# AD5686R.net
KiCad netlist of a schematic drawn in Altium Designer
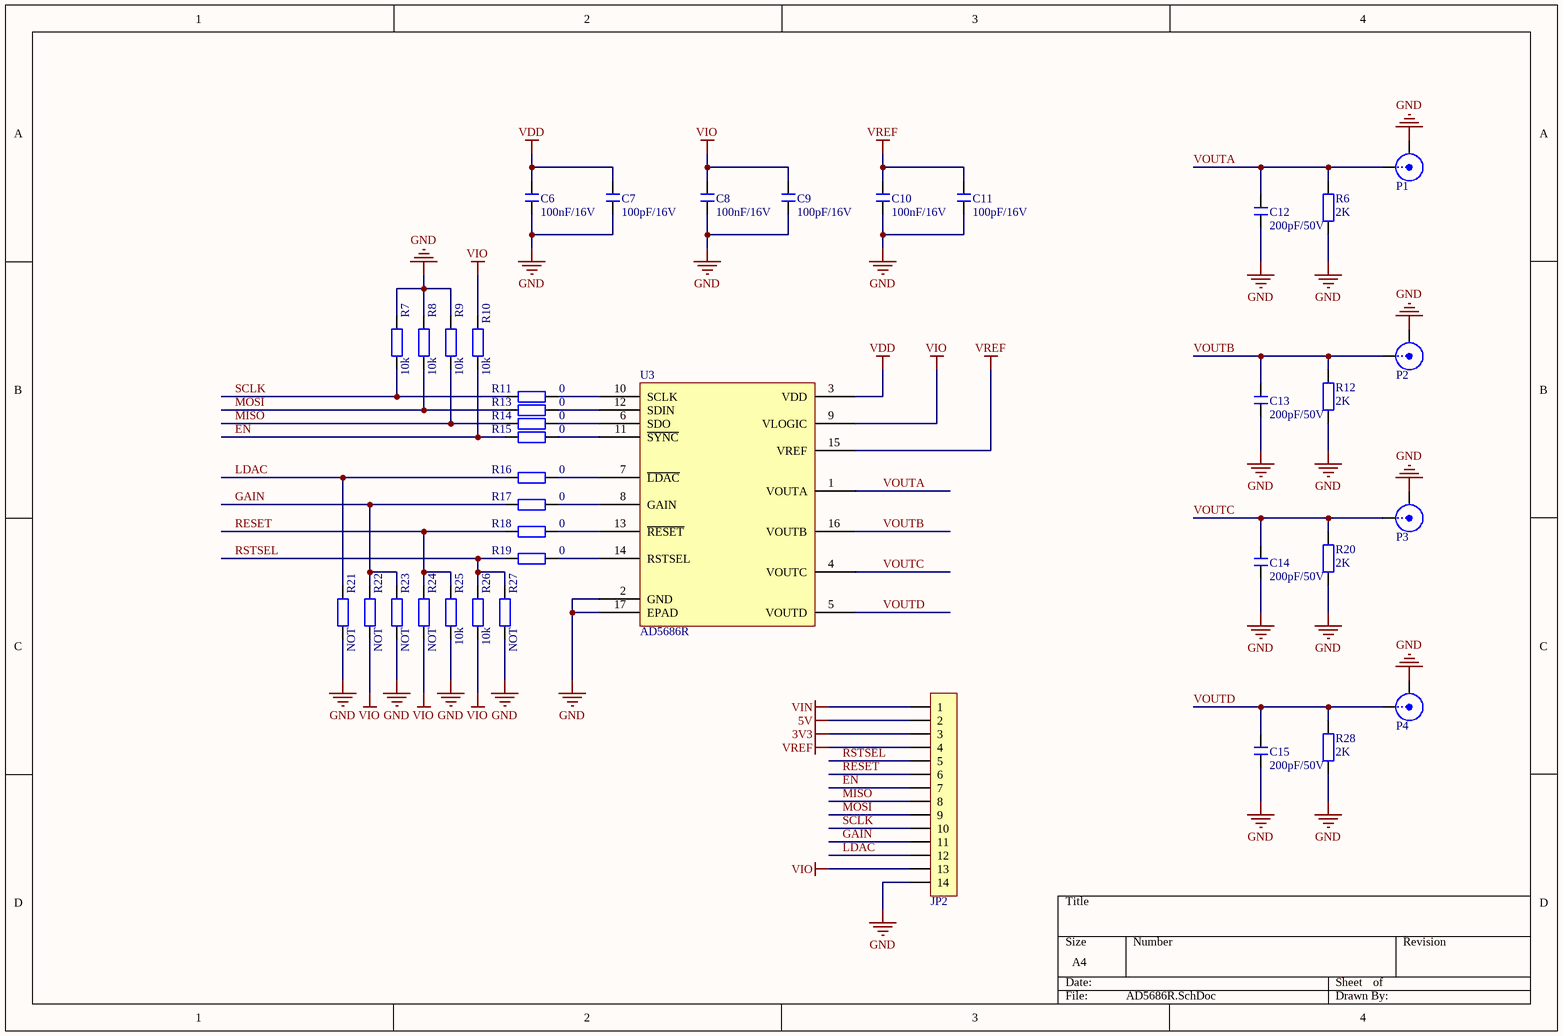
[diagram p0: AD5686R.SchDoc]

(export (version "E")
  (design (tool "Eeschema 10.0.6"))
  (components
    (comp (ref "C6")
      (value "100nF/16V")
      (footprint "C 0402_L")
      (description "贴片电容")
      (libsource (lib "3.1   - 电阻-电容-电感") (part "C"))
    )
    (comp (ref "C7")
      (value "100pF/16V")
      (footprint "C 0402_L")
      (description "贴片电容")
      (libsource (lib "3.1   - 电阻-电容-电感") (part "C"))
    )
    (comp (ref "C8")
      (value "100nF/16V")
      (footprint "C 0402_L")
      (description "贴片电容")
      (libsource (lib "3.1   - 电阻-电容-电感") (part "C"))
    )
    (comp (ref "C9")
      (value "100pF/16V")
      (footprint "C 0402_L")
      (description "贴片电容")
      (libsource (lib "3.1   - 电阻-电容-电感") (part "C"))
    )
    (comp (ref "C10")
      (value "100nF/16V")
      (footprint "C 0402_L")
      (description "贴片电容")
      (libsource (lib "3.1   - 电阻-电容-电感") (part "C"))
    )
    (comp (ref "C11")
      (value "100pF/16V")
      (footprint "C 0402_L")
      (description "贴片电容")
      (libsource (lib "3.1   - 电阻-电容-电感") (part "C"))
    )
    (comp (ref "C12")
      (value "200pF/50V")
      (footprint "C 0402_L")
      (description "贴片电容")
      (libsource (lib "3.1   - 电阻-电容-电感") (part "C"))
    )
    (comp (ref "C13")
      (value "200pF/50V")
      (footprint "C 0402_L")
      (description "贴片电容")
      (libsource (lib "3.1   - 电阻-电容-电感") (part "C"))
    )
    (comp (ref "C14")
      (value "200pF/50V")
      (footprint "C 0402_L")
      (description "贴片电容")
      (libsource (lib "3.1   - 电阻-电容-电感") (part "C"))
    )
    (comp (ref "C15")
      (value "200pF/50V")
      (footprint "C 0402_L")
      (description "贴片电容")
      (libsource (lib "3.1   - 电阻-电容-电感") (part "C"))
    )
    (comp (ref "JP2")
      (value "HDR-1X14")
      (footprint "HDR2.54-LI-14P")
      (description "14P接插件")
      (fields (field (name "版权归属") "源创客"))
      (libsource (lib "4.5   - 接插件-脚距2.54") (part "Header 14"))
    )
    (comp (ref "P1")
      (value "SMB")
      (footprint "SMA")
      (description "SMB Straight Connector")
      (libsource (lib "Miscellaneous Connectors") (part "SMB"))
    )
    (comp (ref "P2")
      (value "SMB")
      (footprint "SMA")
      (description "SMB Straight Connector")
      (libsource (lib "Miscellaneous Connectors") (part "SMB"))
    )
    (comp (ref "P3")
      (value "SMB")
      (footprint "SMA")
      (description "SMB Straight Connector")
      (libsource (lib "Miscellaneous Connectors") (part "SMB"))
    )
    (comp (ref "P4")
      (value "SMB")
      (footprint "SMA")
      (description "SMB Straight Connector")
      (libsource (lib "Miscellaneous Connectors") (part "SMB"))
    )
    (comp (ref "R6")
      (value "2K")
      (footprint "R 0402_L")
      (description "贴片电阻 0402 1%")
      (libsource (lib "3.1   - 电阻-电容-电感") (part "R"))
    )
    (comp (ref "R7")
      (value "10k")
      (footprint "R 0402_L")
      (description "贴片电阻")
      (libsource (lib "3.1   - 电阻-电容-电感") (part "R"))
    )
    (comp (ref "R8")
      (value "10k")
      (footprint "R 0402_L")
      (description "贴片电阻")
      (libsource (lib "3.1   - 电阻-电容-电感") (part "R"))
    )
    (comp (ref "R9")
      (value "10k")
      (footprint "R 0402_L")
      (description "贴片电阻")
      (libsource (lib "3.1   - 电阻-电容-电感") (part "R"))
    )
    (comp (ref "R10")
      (value "10k")
      (footprint "R 0402_L")
      (description "贴片电阻")
      (libsource (lib "3.1   - 电阻-电容-电感") (part "R"))
    )
    (comp (ref "R11")
      (value "0")
      (footprint "R 0402_L")
      (description "贴片电阻 0402 1%")
      (libsource (lib "3.1   - 电阻-电容-电感") (part "R"))
    )
    (comp (ref "R12")
      (value "2K")
      (footprint "R 0402_L")
      (description "贴片电阻 0402 1%")
      (libsource (lib "3.1   - 电阻-电容-电感") (part "R"))
    )
    (comp (ref "R13")
      (value "0")
      (footprint "R 0402_L")
      (description "贴片电阻 0402 1%")
      (libsource (lib "3.1   - 电阻-电容-电感") (part "R"))
    )
    (comp (ref "R14")
      (value "0")
      (footprint "R 0402_L")
      (description "贴片电阻 0402 1%")
      (libsource (lib "3.1   - 电阻-电容-电感") (part "R"))
    )
    (comp (ref "R15")
      (value "0")
      (footprint "R 0402_L")
      (description "贴片电阻 0402 1%")
      (libsource (lib "3.1   - 电阻-电容-电感") (part "R"))
    )
    (comp (ref "R16")
      (value "0")
      (footprint "R 0402_L")
      (description "贴片电阻 0402 1%")
      (libsource (lib "3.1   - 电阻-电容-电感") (part "R"))
    )
    (comp (ref "R17")
      (value "0")
      (footprint "R 0402_L")
      (description "贴片电阻 0402 1%")
      (libsource (lib "3.1   - 电阻-电容-电感") (part "R"))
    )
    (comp (ref "R18")
      (value "0")
      (footprint "R 0402_L")
      (description "贴片电阻 0402 1%")
      (libsource (lib "3.1   - 电阻-电容-电感") (part "R"))
    )
    (comp (ref "R19")
      (value "0")
      (footprint "R 0402_L")
      (description "贴片电阻 0402 1%")
      (libsource (lib "3.1   - 电阻-电容-电感") (part "R"))
    )
    (comp (ref "R20")
      (value "2K")
      (footprint "R 0402_L")
      (description "贴片电阻 0402 1%")
      (libsource (lib "3.1   - 电阻-电容-电感") (part "R"))
    )
    (comp (ref "R21")
      (value "NOT")
      (footprint "R 0402_L")
      (description "贴片电阻")
      (libsource (lib "3.1   - 电阻-电容-电感") (part "R"))
    )
    (comp (ref "R22")
      (value "NOT")
      (footprint "R 0402_L")
      (description "贴片电阻")
      (libsource (lib "3.1   - 电阻-电容-电感") (part "R"))
    )
    (comp (ref "R23")
      (value "NOT")
      (footprint "R 0402_L")
      (description "贴片电阻")
      (libsource (lib "3.1   - 电阻-电容-电感") (part "R"))
    )
    (comp (ref "R24")
      (value "NOT")
      (footprint "R 0402_L")
      (description "贴片电阻")
      (libsource (lib "3.1   - 电阻-电容-电感") (part "R"))
    )
    (comp (ref "R25")
      (value "10k")
      (footprint "R 0402_L")
      (description "贴片电阻")
      (libsource (lib "3.1   - 电阻-电容-电感") (part "R"))
    )
    (comp (ref "R26")
      (value "10k")
      (footprint "R 0402_L")
      (description "贴片电阻")
      (libsource (lib "3.1   - 电阻-电容-电感") (part "R"))
    )
    (comp (ref "R27")
      (value "NOT")
      (footprint "R 0402_L")
      (description "贴片电阻")
      (libsource (lib "3.1   - 电阻-电容-电感") (part "R"))
    )
    (comp (ref "R28")
      (value "2K")
      (footprint "R 0402_L")
      (description "贴片电阻 0402 1%")
      (libsource (lib "3.1   - 电阻-电容-电感") (part "R"))
    )
    (comp (ref "U3") (value "AD5686R") (footprint "AD5686R") (libsource (lib "Schlib1") (part "AD5686R")))
  )
  (nets
    (net (code "1") (name "/EN") (class "Default")
      (node (ref "JP2") (pin "7") (pinfunction "7_7") (pintype "passive"))
      (node (ref "R10") (pin "2") (pinfunction "2_2") (pintype "passive"))
      (node (ref "R15") (pin "2") (pinfunction "2_2") (pintype "passive"))
    )
    (net (code "2") (name "/GAIN") (class "Default")
      (node (ref "JP2") (pin "11") (pinfunction "11_11") (pintype "passive"))
      (node (ref "R17") (pin "2") (pinfunction "2_2") (pintype "passive"))
      (node (ref "R22") (pin "2") (pinfunction "2_2") (pintype "passive"))
      (node (ref "R23") (pin "2") (pinfunction "2_2") (pintype "passive"))
    )
    (net (code "3") (name "/LDAC") (class "Default")
      (node (ref "JP2") (pin "12") (pinfunction "12_12") (pintype "passive"))
      (node (ref "R16") (pin "2") (pinfunction "2_2") (pintype "passive"))
      (node (ref "R21") (pin "2") (pinfunction "2_2") (pintype "passive"))
    )
    (net (code "4") (name "/MISO") (class "Default")
      (node (ref "JP2") (pin "8") (pinfunction "8_8") (pintype "passive"))
      (node (ref "R14") (pin "2") (pinfunction "2_2") (pintype "passive"))
      (node (ref "R9") (pin "2") (pinfunction "2_2") (pintype "passive"))
    )
    (net (code "5") (name "/MOSI") (class "Default")
      (node (ref "JP2") (pin "9") (pinfunction "9_9") (pintype "passive"))
      (node (ref "R13") (pin "2") (pinfunction "2_2") (pintype "passive"))
      (node (ref "R8") (pin "2") (pinfunction "2_2") (pintype "passive"))
    )
    (net (code "6") (name "/RESET") (class "Default")
      (node (ref "JP2") (pin "6") (pinfunction "6_6") (pintype "passive"))
      (node (ref "R18") (pin "2") (pinfunction "2_2") (pintype "passive"))
      (node (ref "R24") (pin "2") (pinfunction "2_2") (pintype "passive"))
      (node (ref "R25") (pin "1") (pinfunction "1_1") (pintype "passive"))
    )
    (net (code "7") (name "/RSTSEL") (class "Default")
      (node (ref "JP2") (pin "5") (pinfunction "5_5") (pintype "passive"))
      (node (ref "R19") (pin "2") (pinfunction "2_2") (pintype "passive"))
      (node (ref "R26") (pin "1") (pinfunction "1_1") (pintype "passive"))
      (node (ref "R27") (pin "2") (pinfunction "2_2") (pintype "passive"))
    )
    (net (code "8") (name "/SCLK") (class "Default")
      (node (ref "JP2") (pin "10") (pinfunction "10_10") (pintype "passive"))
      (node (ref "R11") (pin "2") (pinfunction "2_2") (pintype "passive"))
      (node (ref "R7") (pin "2") (pinfunction "2_2") (pintype "passive"))
    )
    (net (code "9") (name "/VOUTA") (class "Default")
      (node (ref "C12") (pin "2") (pinfunction "2_2") (pintype "passive"))
      (node (ref "P1") (pin "1") (pinfunction "X_1") (pintype "passive"))
      (node (ref "R6") (pin "1") (pinfunction "1_1") (pintype "passive"))
      (node (ref "U3") (pin "1") (pinfunction "VOUTA_1") (pintype "passive"))
    )
    (net (code "10") (name "/VOUTB") (class "Default")
      (node (ref "C13") (pin "2") (pinfunction "2_2") (pintype "passive"))
      (node (ref "P2") (pin "1") (pinfunction "X_1") (pintype "passive"))
      (node (ref "R12") (pin "1") (pinfunction "1_1") (pintype "passive"))
      (node (ref "U3") (pin "16") (pinfunction "VOUTB_16") (pintype "passive"))
    )
    (net (code "11") (name "/VOUTC") (class "Default")
      (node (ref "C14") (pin "2") (pinfunction "2_2") (pintype "passive"))
      (node (ref "P3") (pin "1") (pinfunction "X_1") (pintype "passive"))
      (node (ref "R20") (pin "1") (pinfunction "1_1") (pintype "passive"))
      (node (ref "U3") (pin "4") (pinfunction "VOUTC_4") (pintype "passive"))
    )
    (net (code "12") (name "/VOUTD") (class "Default")
      (node (ref "C15") (pin "2") (pinfunction "2_2") (pintype "passive"))
      (node (ref "P4") (pin "1") (pinfunction "X_1") (pintype "passive"))
      (node (ref "R28") (pin "1") (pinfunction "1_1") (pintype "passive"))
      (node (ref "U3") (pin "5") (pinfunction "VOUTD_5") (pintype "passive"))
    )
    (net (code "13") (name "3V3") (class "Default")
      (node (ref "JP2") (pin "3") (pinfunction "3_3") (pintype "passive"))
    )
    (net (code "14") (name "5V") (class "Default")
      (node (ref "JP2") (pin "2") (pinfunction "2_2") (pintype "passive"))
    )
    (net (code "15") (name "GND") (class "Default")
      (node (ref "C10") (pin "1") (pinfunction "1_1") (pintype "passive"))
      (node (ref "C11") (pin "1") (pinfunction "1_1") (pintype "passive"))
      (node (ref "C12") (pin "1") (pinfunction "1_1") (pintype "passive"))
      (node (ref "C13") (pin "1") (pinfunction "1_1") (pintype "passive"))
      (node (ref "C14") (pin "1") (pinfunction "1_1") (pintype "passive"))
      (node (ref "C15") (pin "1") (pinfunction "1_1") (pintype "passive"))
      (node (ref "C6") (pin "1") (pinfunction "1_1") (pintype "passive"))
      (node (ref "C7") (pin "1") (pinfunction "1_1") (pintype "passive"))
      (node (ref "C8") (pin "1") (pinfunction "1_1") (pintype "passive"))
      (node (ref "C9") (pin "1") (pinfunction "1_1") (pintype "passive"))
      (node (ref "JP2") (pin "14") (pinfunction "14_14") (pintype "passive"))
      (node (ref "P1") (pin "2") (pinfunction "Y_2") (pintype "passive"))
      (node (ref "P2") (pin "2") (pinfunction "Y_2") (pintype "passive"))
      (node (ref "P3") (pin "2") (pinfunction "Y_2") (pintype "passive"))
      (node (ref "P4") (pin "2") (pinfunction "Y_2") (pintype "passive"))
      (node (ref "R12") (pin "2") (pinfunction "2_2") (pintype "passive"))
      (node (ref "R20") (pin "2") (pinfunction "2_2") (pintype "passive"))
      (node (ref "R21") (pin "1") (pinfunction "1_1") (pintype "passive"))
      (node (ref "R23") (pin "1") (pinfunction "1_1") (pintype "passive"))
      (node (ref "R25") (pin "2") (pinfunction "2_2") (pintype "passive"))
      (node (ref "R27") (pin "1") (pinfunction "1_1") (pintype "passive"))
      (node (ref "R28") (pin "2") (pinfunction "2_2") (pintype "passive"))
      (node (ref "R6") (pin "2") (pinfunction "2_2") (pintype "passive"))
      (node (ref "R7") (pin "1") (pinfunction "1_1") (pintype "passive"))
      (node (ref "R8") (pin "1") (pinfunction "1_1") (pintype "passive"))
      (node (ref "R9") (pin "1") (pinfunction "1_1") (pintype "passive"))
      (node (ref "U3") (pin "17") (pinfunction "EPAD_17") (pintype "passive"))
      (node (ref "U3") (pin "2") (pinfunction "GND_2") (pintype "passive"))
    )
    (net (code "16") (name "Net-(U3-GAIN)") (class "Default")
      (node (ref "R17") (pin "1") (pinfunction "1_1") (pintype "passive"))
      (node (ref "U3") (pin "8") (pinfunction "GAIN_8") (pintype "passive"))
    )
    (net (code "17") (name "Net-(U3-RSTSEL)") (class "Default")
      (node (ref "R19") (pin "1") (pinfunction "1_1") (pintype "passive"))
      (node (ref "U3") (pin "14") (pinfunction "RSTSEL_14") (pintype "passive"))
    )
    (net (code "18") (name "Net-(U3-SCLK)") (class "Default")
      (node (ref "R11") (pin "1") (pinfunction "1_1") (pintype "passive"))
      (node (ref "U3") (pin "10") (pinfunction "SCLK_10") (pintype "passive"))
    )
    (net (code "19") (name "Net-(U3-SDIN)") (class "Default")
      (node (ref "R13") (pin "1") (pinfunction "1_1") (pintype "passive"))
      (node (ref "U3") (pin "12") (pinfunction "SDIN_12") (pintype "passive"))
    )
    (net (code "20") (name "Net-(U3-SDO)") (class "Default")
      (node (ref "R14") (pin "1") (pinfunction "1_1") (pintype "passive"))
      (node (ref "U3") (pin "6") (pinfunction "SDO_6") (pintype "passive"))
    )
    (net (code "21") (name "Net-(U3-~{LDAC})") (class "Default")
      (node (ref "R16") (pin "1") (pinfunction "1_1") (pintype "passive"))
      (node (ref "U3") (pin "7") (pinfunction "~{LDAC}_7") (pintype "passive"))
    )
    (net (code "22") (name "Net-(U3-~{RESET})") (class "Default")
      (node (ref "R18") (pin "1") (pinfunction "1_1") (pintype "passive"))
      (node (ref "U3") (pin "13") (pinfunction "~{RESET}_13") (pintype "passive"))
    )
    (net (code "23") (name "Net-(U3-~{SYNC})") (class "Default")
      (node (ref "R15") (pin "1") (pinfunction "1_1") (pintype "passive"))
      (node (ref "U3") (pin "11") (pinfunction "~{SYNC}_11") (pintype "passive"))
    )
    (net (code "24") (name "VDD") (class "Default")
      (node (ref "C6") (pin "2") (pinfunction "2_2") (pintype "passive"))
      (node (ref "C7") (pin "2") (pinfunction "2_2") (pintype "passive"))
      (node (ref "U3") (pin "3") (pinfunction "VDD_3") (pintype "passive"))
    )
    (net (code "25") (name "VIN") (class "Default")
      (node (ref "JP2") (pin "1") (pinfunction "1_1") (pintype "passive"))
    )
    (net (code "26") (name "VIO") (class "Default")
      (node (ref "C8") (pin "2") (pinfunction "2_2") (pintype "passive"))
      (node (ref "C9") (pin "2") (pinfunction "2_2") (pintype "passive"))
      (node (ref "JP2") (pin "13") (pinfunction "13_13") (pintype "passive"))
      (node (ref "R10") (pin "1") (pinfunction "1_1") (pintype "passive"))
      (node (ref "R22") (pin "1") (pinfunction "1_1") (pintype "passive"))
      (node (ref "R24") (pin "1") (pinfunction "1_1") (pintype "passive"))
      (node (ref "R26") (pin "2") (pinfunction "2_2") (pintype "passive"))
      (node (ref "U3") (pin "9") (pinfunction "VLOGIC_9") (pintype "passive"))
    )
    (net (code "27") (name "VREF") (class "Default")
      (node (ref "C10") (pin "2") (pinfunction "2_2") (pintype "passive"))
      (node (ref "C11") (pin "2") (pinfunction "2_2") (pintype "passive"))
      (node (ref "JP2") (pin "4") (pinfunction "4_4") (pintype "passive"))
      (node (ref "U3") (pin "15") (pinfunction "VREF_15") (pintype "passive"))
    )
  )
)
